# P1_2025-01-25.net
KiCad netlist of a schematic drawn in EasyEDA Pro
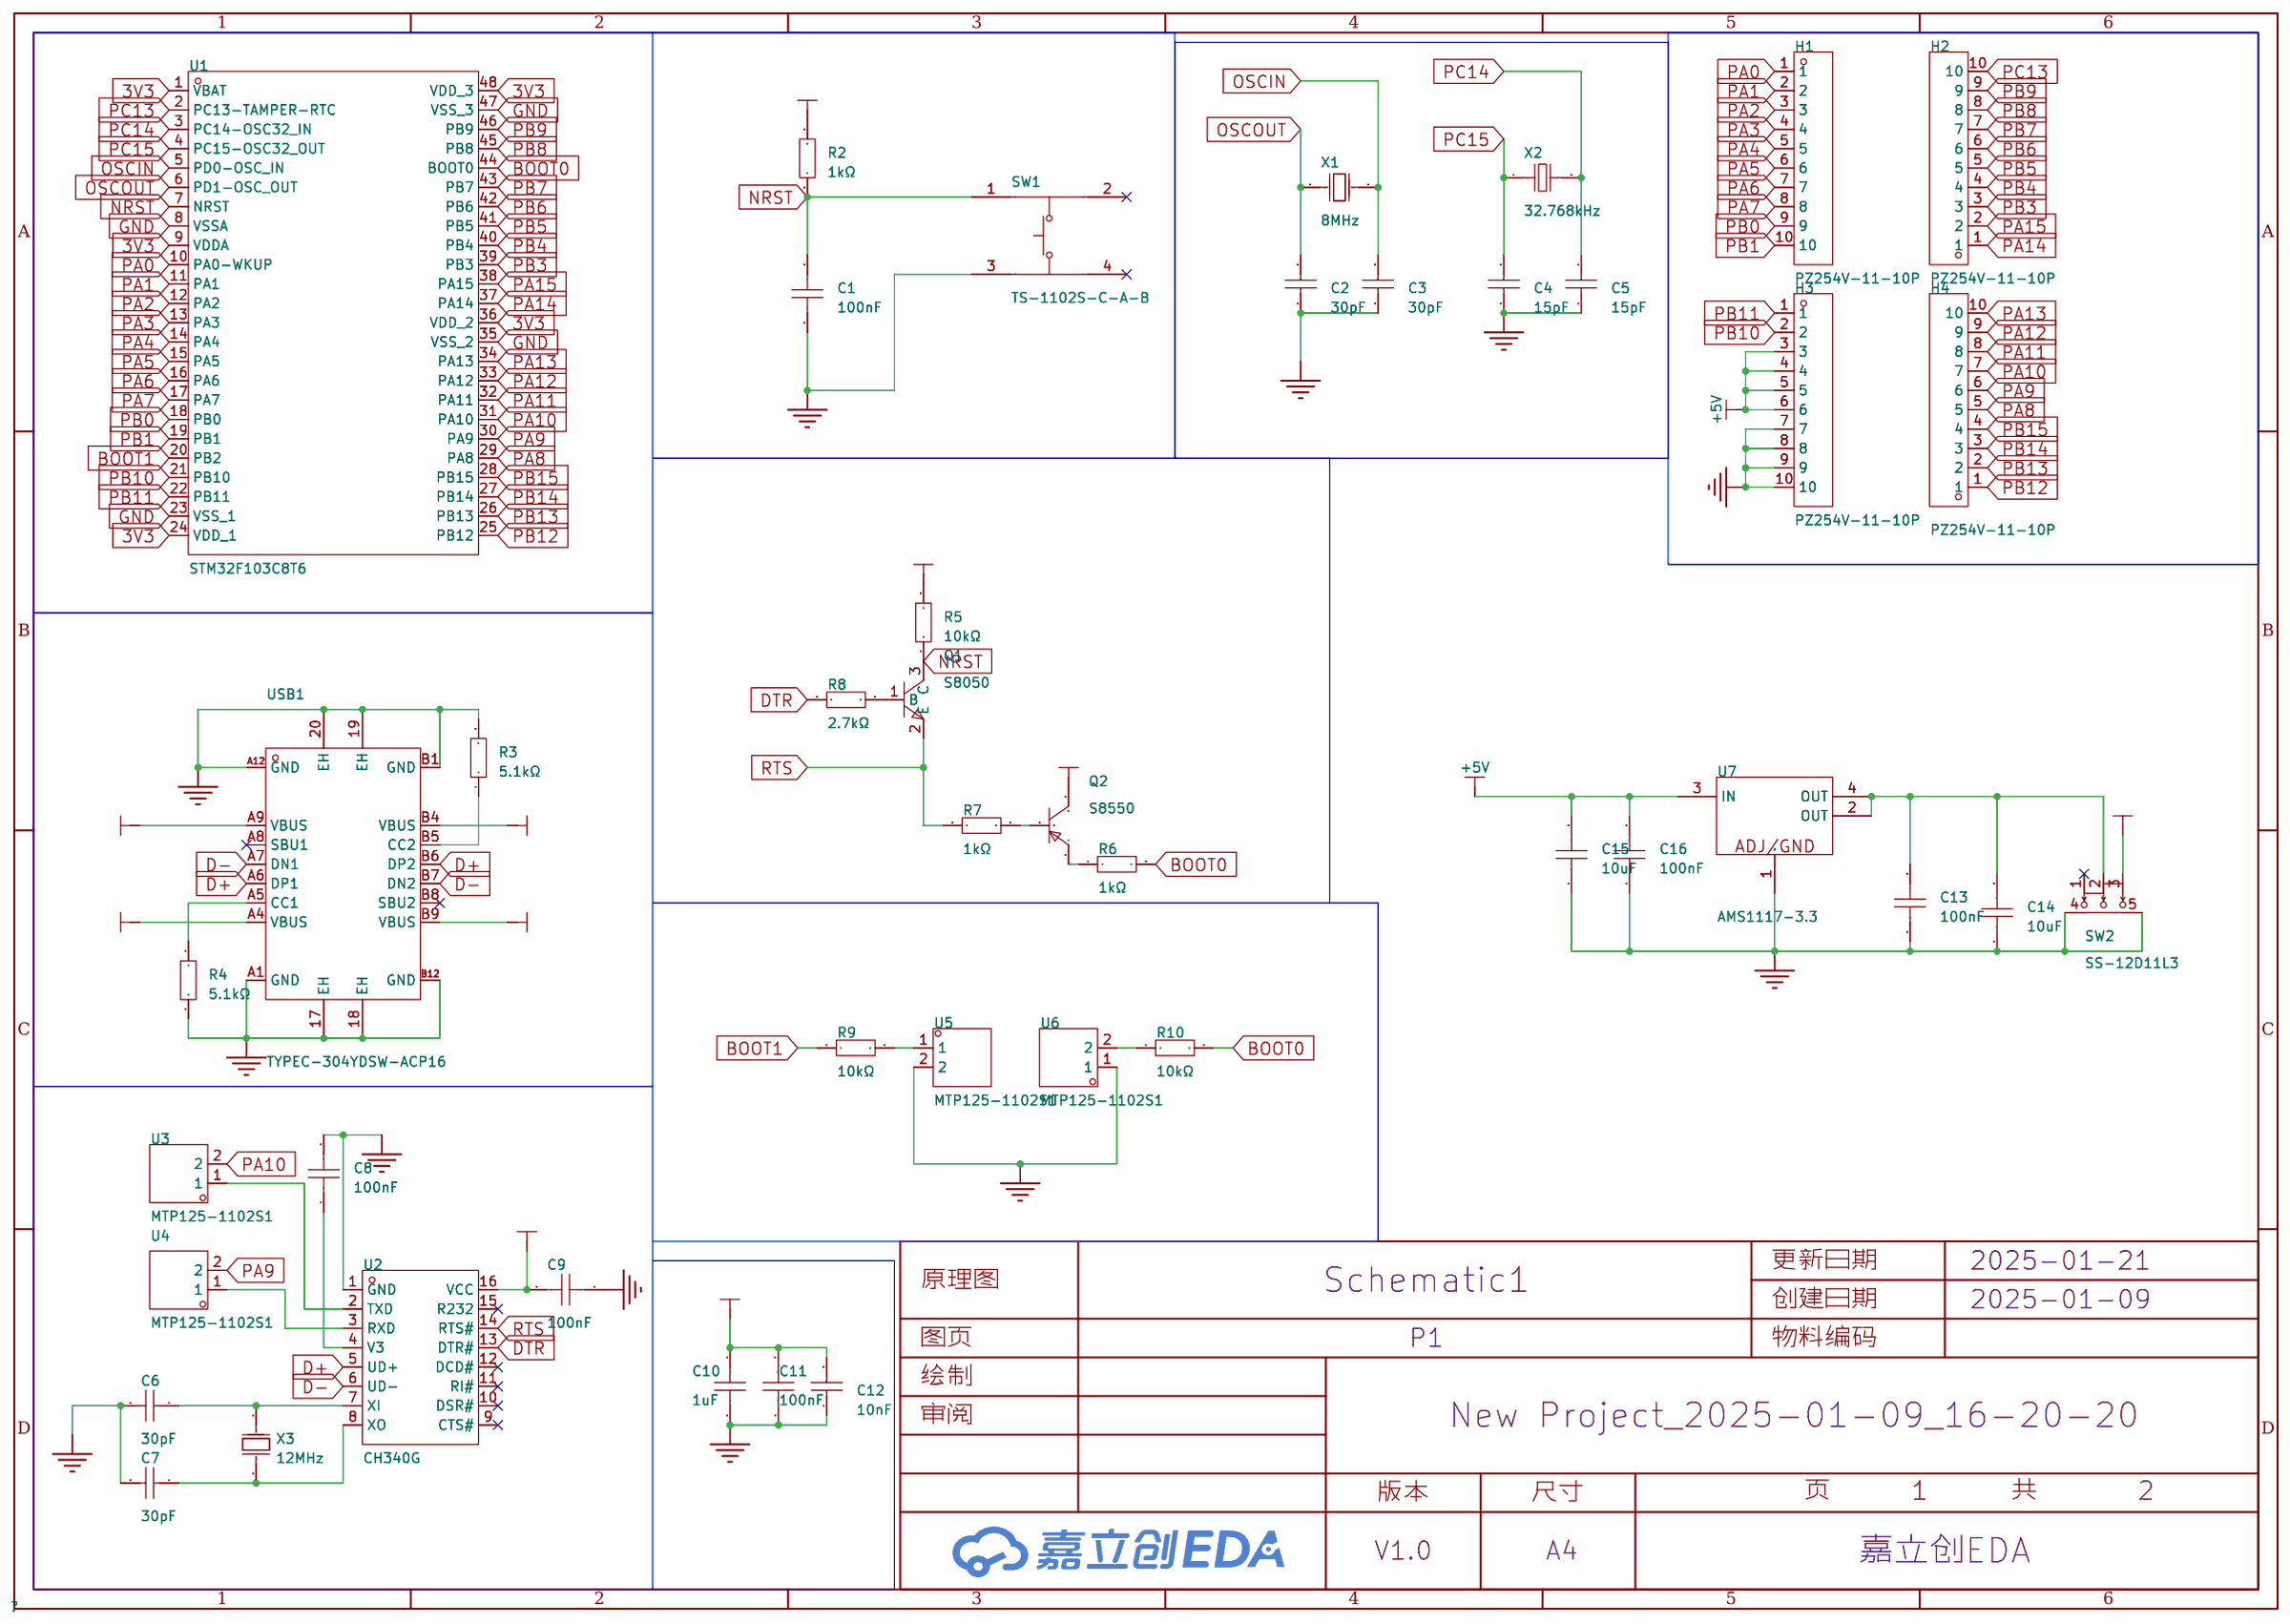
[diagram p0: schematic sheet]

(export (version "E")
  (design (tool "Eeschema 10.0.6"))
  (components
    (comp (ref "C1")
      (value "100nF")
      (footprint "easyedapro:C0603")
      (description "容值:100nF;精度:±10%;额定电压:50V;材质(温度系数):X7R;")
      (fields
        (field (name "Manufacturer Part") "CGA0603X7R104K500JT")
        (field (name "Manufacturer") "HRE(芯声)")
      )
      (libsource (lib "easyedapro") (part "CGA0603X7R104K500JT"))
    )
    (comp (ref "C2")
      (value "30pF")
      (footprint "easyedapro:C0603")
      (description "容值:30pF;精度:±5%;额定电压:50V;材质(温度系数):C0G;")
      (fields (field (name "Manufacturer Part") "0603CG300J500NT") (field (name "Manufacturer") "FH(风华)"))
      (libsource (lib "easyedapro") (part "0603CG300J500NT"))
    )
    (comp (ref "C3")
      (value "30pF")
      (footprint "easyedapro:C0603")
      (description "容值:30pF;精度:±5%;额定电压:50V;材质(温度系数):C0G;")
      (fields (field (name "Manufacturer Part") "0603CG300J500NT") (field (name "Manufacturer") "FH(风华)"))
      (libsource (lib "easyedapro") (part "0603CG300J500NT"))
    )
    (comp (ref "C4")
      (value "15pF")
      (footprint "easyedapro:C0603")
      (description "容值:15pF;精度:±5%;额定电压:50V;材质(温度系数):C0G;")
      (fields
        (field (name "Manufacturer Part") "CL10C150JB8NNNC")
        (field (name "Manufacturer") "SAMSUNG(三星)")
      )
      (libsource (lib "easyedapro") (part "CL10C150JB8NNNC"))
    )
    (comp (ref "C5")
      (value "15pF")
      (footprint "easyedapro:C0603")
      (description "容值:15pF;精度:±5%;额定电压:50V;材质(温度系数):C0G;")
      (fields
        (field (name "Manufacturer Part") "CL10C150JB8NNNC")
        (field (name "Manufacturer") "SAMSUNG(三星)")
      )
      (libsource (lib "easyedapro") (part "CL10C150JB8NNNC"))
    )
    (comp (ref "C6")
      (value "30pF")
      (footprint "easyedapro:C0603")
      (description "容值:30pF;精度:±5%;额定电压:50V;材质(温度系数):C0G;")
      (fields (field (name "Manufacturer Part") "0603CG300J500NT") (field (name "Manufacturer") "FH(风华)"))
      (libsource (lib "easyedapro") (part "0603CG300J500NT"))
    )
    (comp (ref "C7")
      (value "30pF")
      (footprint "easyedapro:C0603")
      (description "容值:30pF;精度:±5%;额定电压:50V;材质(温度系数):C0G;")
      (fields (field (name "Manufacturer Part") "0603CG300J500NT") (field (name "Manufacturer") "FH(风华)"))
      (libsource (lib "easyedapro") (part "0603CG300J500NT"))
    )
    (comp (ref "C8")
      (value "100nF")
      (footprint "easyedapro:C0603")
      (description "容值:100nF;精度:±10%;额定电压:50V;材质(温度系数):X7R;")
      (fields
        (field (name "Manufacturer Part") "CGA0603X7R104K500JT")
        (field (name "Manufacturer") "HRE(芯声)")
      )
      (libsource (lib "easyedapro") (part "CGA0603X7R104K500JT"))
    )
    (comp (ref "C9")
      (value "100nF")
      (footprint "easyedapro:C0603")
      (description "容值:100nF;精度:±10%;额定电压:50V;材质(温度系数):X7R;")
      (fields
        (field (name "Manufacturer Part") "CGA0603X7R104K500JT")
        (field (name "Manufacturer") "HRE(芯声)")
      )
      (libsource (lib "easyedapro") (part "CGA0603X7R104K500JT"))
    )
    (comp (ref "C10")
      (value "1uF")
      (footprint "easyedapro:C0603")
      (description "容值:1uF;精度:±10%;额定电压:50V;材质(温度系数):X5R;")
      (fields
        (field (name "Manufacturer Part") "CL10A105KB8NNNC")
        (field (name "Manufacturer") "SAMSUNG(三星)")
      )
      (libsource (lib "easyedapro") (part "CL10A105KB8NNNC"))
    )
    (comp (ref "C11")
      (value "100nF")
      (footprint "easyedapro:C0603")
      (description "容值:100nF;精度:±10%;额定电压:50V;材质(温度系数):X7R;")
      (fields
        (field (name "Manufacturer Part") "CGA0603X7R104K500JT")
        (field (name "Manufacturer") "HRE(芯声)")
      )
      (libsource (lib "easyedapro") (part "CGA0603X7R104K500JT"))
    )
    (comp (ref "C12")
      (value "10nF")
      (footprint "easyedapro:C0603")
      (description "容值:10nF;精度:±10%;额定电压:50V;材质(温度系数):X7R;")
      (fields
        (field (name "Manufacturer Part") "CC0603KRX7R9BB103")
        (field (name "Manufacturer") "YAGEO(国巨)")
      )
      (libsource (lib "easyedapro") (part "CC0603KRX7R9BB103"))
    )
    (comp (ref "C13")
      (value "100nF")
      (footprint "easyedapro:C0603")
      (description "容值:100nF;精度:±10%;额定电压:50V;材质(温度系数):X7R;")
      (fields
        (field (name "Manufacturer Part") "CGA0603X7R104K500JT")
        (field (name "Manufacturer") "HRE(芯声)")
      )
      (libsource (lib "easyedapro") (part "CGA0603X7R104K500JT"))
    )
    (comp (ref "C14")
      (value "10uF")
      (footprint "easyedapro:C0603")
      (description "容值:10uF;精度:±10%;额定电压:10V;材质(温度系数):X5R;")
      (fields
        (field (name "Manufacturer Part") "CGA0603X5R106K100JT")
        (field (name "Manufacturer") "HRE(芯声)")
      )
      (libsource (lib "easyedapro") (part "CGA0603X5R106K100JT"))
    )
    (comp (ref "C15")
      (value "10uF")
      (footprint "easyedapro:C0603")
      (description "容值:10uF;精度:±10%;额定电压:10V;材质(温度系数):X5R;")
      (fields
        (field (name "Manufacturer Part") "CGA0603X5R106K100JT")
        (field (name "Manufacturer") "HRE(芯声)")
      )
      (libsource (lib "easyedapro") (part "CGA0603X5R106K100JT"))
    )
    (comp (ref "C16")
      (value "100nF")
      (footprint "easyedapro:C0603")
      (description "容值:100nF;精度:±10%;额定电压:50V;材质(温度系数):X7R;")
      (fields
        (field (name "Manufacturer Part") "CGA0603X7R104K500JT")
        (field (name "Manufacturer") "HRE(芯声)")
      )
      (libsource (lib "easyedapro") (part "CGA0603X7R104K500JT"))
    )
    (comp (ref "H1")
      (value "PZ254V-11-10P")
      (footprint "easyedapro:HDR-TH_10P-P2.54-V-M")
      (fields (field (name "Manufacturer") "XFCN(兴飞)"))
      (libsource (lib "easyedapro") (part "PZ254V-11-10P"))
    )
    (comp (ref "H2")
      (value "PZ254V-11-10P")
      (footprint "easyedapro:HDR-TH_10P-P2.54-V-M")
      (fields (field (name "Manufacturer") "XFCN(兴飞)"))
      (libsource (lib "easyedapro") (part "PZ254V-11-10P"))
    )
    (comp (ref "H3")
      (value "PZ254V-11-10P")
      (footprint "easyedapro:HDR-TH_10P-P2.54-V-M")
      (fields (field (name "Manufacturer") "XFCN(兴飞)"))
      (libsource (lib "easyedapro") (part "PZ254V-11-10P"))
    )
    (comp (ref "H4")
      (value "PZ254V-11-10P")
      (footprint "easyedapro:HDR-TH_10P-P2.54-V-M")
      (fields (field (name "Manufacturer") "XFCN(兴飞)"))
      (libsource (lib "easyedapro") (part "PZ254V-11-10P"))
    )
    (comp (ref "Q1")
      (value "S8050")
      (footprint "easyedapro:SOT-23-3_L2.9-W1.3-P1.90-LS2.4-BR")
      (description "晶体管类型:-;集电极电流(Ic):800mA;集射极击穿电压(Vceo):40V;功率(Pd):300mW;直流电流增益(hFE@Ic,Vce):200@50mA,1V;")
      (fields (field (name "Manufacturer") "FOSAN(富信)"))
      (libsource (lib "easyedapro") (part "S8050_C2926165"))
    )
    (comp (ref "Q2")
      (value "S8550")
      (footprint "easyedapro:SOT-23-3_L2.9-W1.3-P1.90-LS2.4-BR")
      (description "晶体管类型:PNP;集电极电流(Ic):500mA;集射极击穿电压(Vceo):25V;功率(Pd):300mW;直流电流增益(hFE@Ic,Vce):120@50mA,1V;")
      (fields (field (name "Manufacturer") "UMW(友台半导体)"))
      (libsource (lib "easyedapro") (part "S8550_C545533"))
    )
    (comp (ref "R2")
      (value "1kΩ")
      (footprint "easyedapro:R0603")
      (description "电阻类型:厚膜电阻;阻值:1kΩ;精度:±1%;功率:100mW;最大工作电压:75V;温度系数:±100ppm/°C;")
      (fields
        (field (name "Manufacturer Part") "0603WAF1001T5E")
        (field (name "Manufacturer") "UNI-ROYAL(厚声)")
      )
      (libsource (lib "easyedapro") (part "0603WAF1001T5E"))
    )
    (comp (ref "R3")
      (value "5.1kΩ")
      (footprint "easyedapro:R0603")
      (description "电阻类型:厚膜电阻;阻值:5.1kΩ;精度:±1%;功率:100mW;最大工作电压:75V;温度系数:±100ppm/°C;")
      (fields
        (field (name "Manufacturer Part") "0603WAF5101T5E")
        (field (name "Manufacturer") "UNI-ROYAL(厚声)")
      )
      (libsource (lib "easyedapro") (part "0603WAF5101T5E"))
    )
    (comp (ref "R4")
      (value "5.1kΩ")
      (footprint "easyedapro:R0603")
      (description "电阻类型:厚膜电阻;阻值:5.1kΩ;精度:±1%;功率:100mW;最大工作电压:75V;温度系数:±100ppm/°C;")
      (fields
        (field (name "Manufacturer Part") "0603WAF5101T5E")
        (field (name "Manufacturer") "UNI-ROYAL(厚声)")
      )
      (libsource (lib "easyedapro") (part "0603WAF5101T5E"))
    )
    (comp (ref "R5")
      (value "10kΩ")
      (footprint "easyedapro:R0603")
      (description "电阻类型:厚膜电阻;阻值:10kΩ;精度:±1%;功率:100mW;最大工作电压:75V;温度系数:±100ppm/°C;")
      (fields
        (field (name "Manufacturer Part") "0603WAF1002T5E")
        (field (name "Manufacturer") "UNI-ROYAL(厚声)")
      )
      (libsource (lib "easyedapro") (part "0603WAF1002T5E"))
    )
    (comp (ref "R6")
      (value "1kΩ")
      (footprint "easyedapro:R0603")
      (description "电阻类型:厚膜电阻;阻值:1kΩ;精度:±1%;功率:100mW;最大工作电压:75V;温度系数:±100ppm/°C;")
      (fields
        (field (name "Manufacturer Part") "0603WAF1001T5E")
        (field (name "Manufacturer") "UNI-ROYAL(厚声)")
      )
      (libsource (lib "easyedapro") (part "0603WAF1001T5E"))
    )
    (comp (ref "R7")
      (value "1kΩ")
      (footprint "easyedapro:R0603")
      (description "电阻类型:厚膜电阻;阻值:1kΩ;精度:±1%;功率:100mW;最大工作电压:75V;温度系数:±100ppm/°C;")
      (fields
        (field (name "Manufacturer Part") "0603WAF1001T5E")
        (field (name "Manufacturer") "UNI-ROYAL(厚声)")
      )
      (libsource (lib "easyedapro") (part "0603WAF1001T5E"))
    )
    (comp (ref "R8")
      (value "2.7kΩ")
      (footprint "easyedapro:R0603")
      (description "电阻类型:厚膜电阻;阻值:2.7kΩ;精度:±1%;功率:100mW;最大工作电压:75V;温度系数:±100ppm/°C;")
      (fields
        (field (name "Manufacturer Part") "0603WAF2701T5E")
        (field (name "Manufacturer") "UNI-ROYAL(厚声)")
      )
      (libsource (lib "easyedapro") (part "0603WAF2701T5E"))
    )
    (comp (ref "R9")
      (value "10kΩ")
      (footprint "easyedapro:R0603")
      (description "电阻类型:厚膜电阻;阻值:10kΩ;精度:±1%;功率:100mW;最大工作电压:75V;温度系数:±100ppm/°C;")
      (fields
        (field (name "Manufacturer Part") "0603WAF1002T5E")
        (field (name "Manufacturer") "UNI-ROYAL(厚声)")
      )
      (libsource (lib "easyedapro") (part "0603WAF1002T5E"))
    )
    (comp (ref "R10")
      (value "10kΩ")
      (footprint "easyedapro:R0603")
      (description "电阻类型:厚膜电阻;阻值:10kΩ;精度:±1%;功率:100mW;最大工作电压:75V;温度系数:±100ppm/°C;")
      (fields
        (field (name "Manufacturer Part") "0603WAF1002T5E")
        (field (name "Manufacturer") "UNI-ROYAL(厚声)")
      )
      (libsource (lib "easyedapro") (part "0603WAF1002T5E"))
    )
    (comp (ref "SW1")
      (value "TS-1102S-C-A-B")
      (footprint "easyedapro:KEY-SMD_4P-L6.0-W6.0-P4.50-LS8.6")
      (fields (field (name "Manufacturer") "XKB Connectivity(中国星坤)"))
      (libsource (lib "easyedapro") (part "TS-1102S-C-A-B"))
    )
    (comp (ref "SW2")
      (value "SS-12D11L3")
      (footprint "easyedapro:SW-TH_SS-12D11L3")
      (description "电路结构:单刀双掷;安装方式:弯插;开关颜色:黑色;额定电流(DC):3A;额定电压(DC):125V;额定电流(AC):3A;额定电压(AC):125V;机械寿命:1万次;")
      (fields (field (name "Manufacturer") "XKB Connectivity(中国星坤)"))
      (libsource (lib "easyedapro") (part "SS-12D11L3"))
    )
    (comp (ref "U1")
      (value "STM32F103C8T6")
      (footprint "easyedapro:LQFP-48_L7.0-W7.0-P0.50-LS9.0-BL")
      (description "CPU内核:ARM-M3;CPU最大主频:72MHz;应用领域:-;")
      (fields (field (name "Manufacturer") "ST(意法半导体)"))
      (libsource (lib "easyedapro") (part "STM32F103C8T6"))
    )
    (comp (ref "U2")
      (value "CH340G")
      (footprint "easyedapro:SOIC-16_L9.9-W3.9-P1.27-LS6.0-BL")
      (description "应用功能:USB转UART;接口协议:USB 2.0;数据速率:2Mbps;")
      (fields (field (name "Manufacturer") "WCH(南京沁恒)"))
      (libsource (lib "easyedapro") (part "CH340G"))
    )
    (comp (ref "U3")
      (value "MTP125-1102S1")
      (footprint "easyedapro:HDR-TH_2P-P2.54-V-M-1")
      (fields (field (name "Manufacturer") "MINTRON(明硕)"))
      (libsource (lib "easyedapro") (part "MTP125-1102S1"))
    )
    (comp (ref "U4")
      (value "MTP125-1102S1")
      (footprint "easyedapro:HDR-TH_2P-P2.54-V-M-1")
      (fields (field (name "Manufacturer") "MINTRON(明硕)"))
      (libsource (lib "easyedapro") (part "MTP125-1102S1"))
    )
    (comp (ref "U5")
      (value "MTP125-1102S1")
      (footprint "easyedapro:HDR-TH_2P-P2.54-V-M-1")
      (fields (field (name "Manufacturer") "MINTRON(明硕)"))
      (libsource (lib "easyedapro") (part "MTP125-1102S1"))
    )
    (comp (ref "U6")
      (value "MTP125-1102S1")
      (footprint "easyedapro:HDR-TH_2P-P2.54-V-M-1")
      (fields (field (name "Manufacturer") "MINTRON(明硕)"))
      (libsource (lib "easyedapro") (part "MTP125-1102S1"))
    )
    (comp (ref "U7")
      (value "AMS1117-3.3")
      (footprint "easyedapro:SOT-223-3_L6.4-W3.5-P2.30-LS7.0-BR")
      (fields (field (name "Manufacturer") "国芯佳品"))
      (libsource (lib "easyedapro") (part "AMS1117-3.3_C2992570"))
    )
    (comp (ref "USB1")
      (value "TYPEC-304YDSW-ACP16")
      (footprint "easyedapro:USB-C-SMD_TYPEC-304YDSW-ACP16")
      (fields (field (name "Manufacturer") "XUNPU(讯普)"))
      (libsource (lib "easyedapro") (part "TYPEC-304YDSW-ACP16"))
    )
    (comp (ref "X1")
      (value "8MHz")
      (footprint "easyedapro:OSC-TH_L10.0-W4.5-P5.00")
      (description "晶振类型:直插晶振;频率:8MHz;常温频差:±20ppm;外接负载电容:20pF;频率稳定度(全温):±30ppm;")
      (fields (field (name "Manufacturer Part") "X49SD8MSD2SC") (field (name "Manufacturer") "YXC(扬兴晶振)"))
      (libsource (lib "easyedapro") (part "X49SD8MSD2SC"))
    )
    (comp (ref "X2")
      (value "32.768kHz")
      (footprint "easyedapro:CRYSTAL-SMD_L7.0-W3.2-LS7.5")
      (description "频率:32.768kHz;常温频差:±20ppm;外接负载电容:12.5pF;频率稳定度(全温):±10ppm;")
      (fields
        (field (name "Manufacturer Part") "HY32768KSMD3068YA2R30")
        (field (name "Manufacturer") "Huiyuan crystal(惠源晶工)")
      )
      (libsource (lib "easyedapro") (part "HY32768KSMD3068YA2R30"))
    )
    (comp (ref "X3")
      (value "12MHz")
      (footprint "easyedapro:HC-49US_L11.5-W4.5-P4.88")
      (description "晶振类型:直插晶振;频率:12MHz;常温频差:±20ppm;外接负载电容:20pF;频率稳定度(全温):±30ppm;")
      (fields (field (name "Manufacturer Part") "X49SD12MSD2SC") (field (name "Manufacturer") "YXC(扬兴晶振)"))
      (libsource (lib "easyedapro") (part "X49SD12MSD2SC"))
    )
  )
  (nets
    (net (code "1") (name "+5V") (class "Default")
      (node (ref "C15") (pin "2") (pinfunction "2_2") (pintype "unspecified"))
      (node (ref "C16") (pin "2") (pinfunction "2_2") (pintype "unspecified"))
      (node (ref "H3") (pin "3") (pinfunction "3_3") (pintype "unspecified"))
      (node (ref "H3") (pin "4") (pinfunction "4_4") (pintype "unspecified"))
      (node (ref "H3") (pin "5") (pinfunction "5_5") (pintype "unspecified"))
      (node (ref "H3") (pin "6") (pinfunction "6_6") (pintype "unspecified"))
      (node (ref "U7") (pin "3") (pinfunction "IN_3") (pintype "unspecified"))
    )
    (net (code "2") (name "+5VUSB") (class "Default")
      (node (ref "C9") (pin "2") (pinfunction "2_2") (pintype "unspecified"))
      (node (ref "U2") (pin "16") (pinfunction "VCC_16") (pintype "unspecified"))
      (node (ref "USB1") (pin "A4") (pinfunction "VBUS_A4") (pintype "unspecified"))
      (node (ref "USB1") (pin "A9") (pinfunction "VBUS_A9") (pintype "unspecified"))
      (node (ref "USB1") (pin "B4") (pinfunction "VBUS_B4") (pintype "unspecified"))
      (node (ref "USB1") (pin "B9") (pinfunction "VBUS_B9") (pintype "unspecified"))
    )
    (net (code "3") (name "3V3") (class "Default")
      (node (ref "C10") (pin "2") (pinfunction "2_2") (pintype "unspecified"))
      (node (ref "C11") (pin "2") (pinfunction "2_2") (pintype "unspecified"))
      (node (ref "C12") (pin "2") (pinfunction "2_2") (pintype "input"))
      (node (ref "Q2") (pin "3") (pinfunction "C_3") (pintype "input"))
      (node (ref "R2") (pin "2") (pinfunction "2_2") (pintype "input"))
      (node (ref "R5") (pin "2") (pinfunction "2_2") (pintype "input"))
      (node (ref "SW2") (pin "3") (pinfunction "3_3") (pintype "unspecified"))
      (node (ref "U1") (pin "1") (pinfunction "VBAT_1") (pintype "unspecified"))
      (node (ref "U1") (pin "24") (pinfunction "VDD_1_24") (pintype "unspecified"))
      (node (ref "U1") (pin "36") (pinfunction "VDD_2_36") (pintype "unspecified"))
      (node (ref "U1") (pin "48") (pinfunction "VDD_3_48") (pintype "unspecified"))
      (node (ref "U1") (pin "9") (pinfunction "VDDA_9") (pintype "unspecified"))
    )
    (net (code "4") (name "BOOT0") (class "Default")
      (node (ref "R10") (pin "2") (pinfunction "2_2") (pintype "input"))
      (node (ref "R6") (pin "2") (pinfunction "2_2") (pintype "input"))
      (node (ref "U1") (pin "44") (pinfunction "BOOT0_44") (pintype "unspecified"))
    )
    (net (code "5") (name "BOOT1") (class "Default")
      (node (ref "R9") (pin "1") (pinfunction "1_1") (pintype "input"))
      (node (ref "U1") (pin "20") (pinfunction "PB2_20") (pintype "unspecified"))
    )
    (net (code "6") (name "D+") (class "Default")
      (node (ref "U2") (pin "5") (pinfunction "UD+_5") (pintype "unspecified"))
      (node (ref "USB1") (pin "A6") (pinfunction "DP1_A6") (pintype "unspecified"))
      (node (ref "USB1") (pin "B6") (pinfunction "DP2_B6") (pintype "unspecified"))
    )
    (net (code "7") (name "D-") (class "Default")
      (node (ref "U2") (pin "6") (pinfunction "UD-_6") (pintype "unspecified"))
      (node (ref "USB1") (pin "A7") (pinfunction "DN1_A7") (pintype "unspecified"))
      (node (ref "USB1") (pin "B7") (pinfunction "DN2_B7") (pintype "unspecified"))
    )
    (net (code "8") (name "DTR") (class "Default")
      (node (ref "R8") (pin "1") (pinfunction "1_1") (pintype "input"))
      (node (ref "U2") (pin "13") (pinfunction "DTR#_13") (pintype "unspecified"))
    )
    (net (code "9") (name "GND") (class "Default")
      (node (ref "C1") (pin "1") (pinfunction "1_1") (pintype "unspecified"))
      (node (ref "C10") (pin "1") (pinfunction "1_1") (pintype "unspecified"))
      (node (ref "C11") (pin "1") (pinfunction "1_1") (pintype "unspecified"))
      (node (ref "C12") (pin "1") (pinfunction "1_1") (pintype "input"))
      (node (ref "C13") (pin "1") (pinfunction "1_1") (pintype "unspecified"))
      (node (ref "C14") (pin "1") (pinfunction "1_1") (pintype "unspecified"))
      (node (ref "C15") (pin "1") (pinfunction "1_1") (pintype "unspecified"))
      (node (ref "C16") (pin "1") (pinfunction "1_1") (pintype "unspecified"))
      (node (ref "C2") (pin "1") (pinfunction "1_1") (pintype "input"))
      (node (ref "C3") (pin "1") (pinfunction "1_1") (pintype "input"))
      (node (ref "C4") (pin "1") (pinfunction "1_1") (pintype "input"))
      (node (ref "C5") (pin "1") (pinfunction "1_1") (pintype "input"))
      (node (ref "C6") (pin "2") (pinfunction "2_2") (pintype "input"))
      (node (ref "C7") (pin "2") (pinfunction "2_2") (pintype "input"))
      (node (ref "C8") (pin "2") (pinfunction "2_2") (pintype "unspecified"))
      (node (ref "C9") (pin "1") (pinfunction "1_1") (pintype "unspecified"))
      (node (ref "H3") (pin "10") (pinfunction "10_10") (pintype "unspecified"))
      (node (ref "H3") (pin "7") (pinfunction "7_7") (pintype "unspecified"))
      (node (ref "H3") (pin "8") (pinfunction "8_8") (pintype "unspecified"))
      (node (ref "H3") (pin "9") (pinfunction "9_9") (pintype "unspecified"))
      (node (ref "R3") (pin "2") (pinfunction "2_2") (pintype "input"))
      (node (ref "R4") (pin "1") (pinfunction "1_1") (pintype "input"))
      (node (ref "SW1") (pin "3") (pinfunction "3_3") (pintype "unspecified"))
      (node (ref "SW2") (pin "4") (pinfunction "4_4") (pintype "unspecified"))
      (node (ref "SW2") (pin "5") (pinfunction "5_5") (pintype "unspecified"))
      (node (ref "U1") (pin "23") (pinfunction "VSS_1_23") (pintype "unspecified"))
      (node (ref "U1") (pin "35") (pinfunction "VSS_2_35") (pintype "unspecified"))
      (node (ref "U1") (pin "47") (pinfunction "VSS_3_47") (pintype "unspecified"))
      (node (ref "U1") (pin "8") (pinfunction "VSSA_8") (pintype "unspecified"))
      (node (ref "U2") (pin "1") (pinfunction "GND_1") (pintype "unspecified"))
      (node (ref "U5") (pin "2") (pinfunction "2_2") (pintype "unspecified"))
      (node (ref "U6") (pin "1") (pinfunction "1_1") (pintype "unspecified"))
      (node (ref "U7") (pin "1") (pinfunction "ADJ/GND_1") (pintype "unspecified"))
      (node (ref "USB1") (pin "17") (pinfunction "EH_17") (pintype "unspecified"))
      (node (ref "USB1") (pin "18") (pinfunction "EH_18") (pintype "unspecified"))
      (node (ref "USB1") (pin "19") (pinfunction "EH_19") (pintype "unspecified"))
      (node (ref "USB1") (pin "20") (pinfunction "EH_20") (pintype "unspecified"))
      (node (ref "USB1") (pin "A1") (pinfunction "GND_A1") (pintype "unspecified"))
      (node (ref "USB1") (pin "A12") (pinfunction "GND_A12") (pintype "unspecified"))
      (node (ref "USB1") (pin "B1") (pinfunction "GND_B1") (pintype "unspecified"))
      (node (ref "USB1") (pin "B12") (pinfunction "GND_B12") (pintype "unspecified"))
    )
    (net (code "10") (name "NRST") (class "Default")
      (node (ref "C1") (pin "2") (pinfunction "2_2") (pintype "unspecified"))
      (node (ref "Q1") (pin "3") (pinfunction "C_3") (pintype "input"))
      (node (ref "R2") (pin "1") (pinfunction "1_1") (pintype "input"))
      (node (ref "R5") (pin "1") (pinfunction "1_1") (pintype "input"))
      (node (ref "SW1") (pin "1") (pinfunction "1_1") (pintype "unspecified"))
      (node (ref "U1") (pin "7") (pinfunction "NRST_7") (pintype "unspecified"))
    )
    (net (code "11") (name "Net-(C13-Pad2)") (class "Default")
      (node (ref "C13") (pin "2") (pinfunction "2_2") (pintype "unspecified"))
      (node (ref "C14") (pin "2") (pinfunction "2_2") (pintype "unspecified"))
      (node (ref "SW2") (pin "2") (pinfunction "2_2") (pintype "unspecified"))
      (node (ref "U7") (pin "2") (pinfunction "OUT_2") (pintype "unspecified"))
      (node (ref "U7") (pin "4") (pinfunction "OUT_4") (pintype "unspecified"))
    )
    (net (code "12") (name "Net-(Q1-B)") (class "Default")
      (node (ref "Q1") (pin "1") (pinfunction "B_1") (pintype "input"))
      (node (ref "R8") (pin "2") (pinfunction "2_2") (pintype "input"))
    )
    (net (code "13") (name "Net-(Q2-B)") (class "Default")
      (node (ref "Q2") (pin "1") (pinfunction "B_1") (pintype "input"))
      (node (ref "R7") (pin "2") (pinfunction "2_2") (pintype "input"))
    )
    (net (code "14") (name "Net-(Q2-E)") (class "Default")
      (node (ref "Q2") (pin "2") (pinfunction "E_2") (pintype "input"))
      (node (ref "R6") (pin "1") (pinfunction "1_1") (pintype "input"))
    )
    (net (code "15") (name "Net-(R9-Pad2)") (class "Default")
      (node (ref "R9") (pin "2") (pinfunction "2_2") (pintype "input"))
      (node (ref "U5") (pin "1") (pinfunction "1_1") (pintype "unspecified"))
    )
    (net (code "16") (name "Net-(R10-Pad1)") (class "Default")
      (node (ref "R10") (pin "1") (pinfunction "1_1") (pintype "input"))
      (node (ref "U6") (pin "2") (pinfunction "2_2") (pintype "unspecified"))
    )
    (net (code "17") (name "Net-(U2-RXD)") (class "Default")
      (node (ref "U2") (pin "3") (pinfunction "RXD_3") (pintype "unspecified"))
      (node (ref "U4") (pin "1") (pinfunction "1_1") (pintype "unspecified"))
    )
    (net (code "18") (name "Net-(U2-TXD)") (class "Default")
      (node (ref "U2") (pin "2") (pinfunction "TXD_2") (pintype "unspecified"))
      (node (ref "U3") (pin "1") (pinfunction "1_1") (pintype "unspecified"))
    )
    (net (code "19") (name "Net-(U2-V3)") (class "Default")
      (node (ref "C8") (pin "1") (pinfunction "1_1") (pintype "unspecified"))
      (node (ref "U2") (pin "4") (pinfunction "V3_4") (pintype "unspecified"))
    )
    (net (code "20") (name "Net-(U2-XI)") (class "Default")
      (node (ref "C6") (pin "1") (pinfunction "1_1") (pintype "input"))
      (node (ref "U2") (pin "7") (pinfunction "XI_7") (pintype "unspecified"))
      (node (ref "X3") (pin "1") (pinfunction "OSC1_1") (pintype "input"))
    )
    (net (code "21") (name "Net-(U2-XO)") (class "Default")
      (node (ref "C7") (pin "1") (pinfunction "1_1") (pintype "input"))
      (node (ref "U2") (pin "8") (pinfunction "XO_8") (pintype "unspecified"))
      (node (ref "X3") (pin "2") (pinfunction "OSC2_2") (pintype "input"))
    )
    (net (code "22") (name "Net-(USB1-CC1)") (class "Default")
      (node (ref "R4") (pin "2") (pinfunction "2_2") (pintype "input"))
      (node (ref "USB1") (pin "A5") (pinfunction "CC1_A5") (pintype "unspecified"))
    )
    (net (code "23") (name "Net-(USB1-CC2)") (class "Default")
      (node (ref "R3") (pin "1") (pinfunction "1_1") (pintype "input"))
      (node (ref "USB1") (pin "B5") (pinfunction "CC2_B5") (pintype "unspecified"))
    )
    (net (code "24") (name "OSCIN") (class "Default")
      (node (ref "C3") (pin "2") (pinfunction "2_2") (pintype "input"))
      (node (ref "U1") (pin "5") (pinfunction "PD0-OSC_IN_5") (pintype "unspecified"))
      (node (ref "X1") (pin "1") (pinfunction "OSC1_1") (pintype "input"))
    )
    (net (code "25") (name "OSCOUT") (class "Default")
      (node (ref "C2") (pin "2") (pinfunction "2_2") (pintype "input"))
      (node (ref "U1") (pin "6") (pinfunction "PD1-OSC_OUT_6") (pintype "unspecified"))
      (node (ref "X1") (pin "2") (pinfunction "OSC2_2") (pintype "input"))
    )
    (net (code "26") (name "PA0") (class "Default")
      (node (ref "H1") (pin "1") (pinfunction "1_1") (pintype "unspecified"))
      (node (ref "U1") (pin "10") (pinfunction "PA0-WKUP_10") (pintype "unspecified"))
    )
    (net (code "27") (name "PA1") (class "Default")
      (node (ref "H1") (pin "2") (pinfunction "2_2") (pintype "unspecified"))
      (node (ref "U1") (pin "11") (pinfunction "PA1_11") (pintype "unspecified"))
    )
    (net (code "28") (name "PA2") (class "Default")
      (node (ref "H1") (pin "3") (pinfunction "3_3") (pintype "unspecified"))
      (node (ref "U1") (pin "12") (pinfunction "PA2_12") (pintype "unspecified"))
    )
    (net (code "29") (name "PA3") (class "Default")
      (node (ref "H1") (pin "4") (pinfunction "4_4") (pintype "unspecified"))
      (node (ref "U1") (pin "13") (pinfunction "PA3_13") (pintype "unspecified"))
    )
    (net (code "30") (name "PA4") (class "Default")
      (node (ref "H1") (pin "5") (pinfunction "5_5") (pintype "unspecified"))
      (node (ref "U1") (pin "14") (pinfunction "PA4_14") (pintype "unspecified"))
    )
    (net (code "31") (name "PA5") (class "Default")
      (node (ref "H1") (pin "6") (pinfunction "6_6") (pintype "unspecified"))
      (node (ref "U1") (pin "15") (pinfunction "PA5_15") (pintype "unspecified"))
    )
    (net (code "32") (name "PA6") (class "Default")
      (node (ref "H1") (pin "7") (pinfunction "7_7") (pintype "unspecified"))
      (node (ref "U1") (pin "16") (pinfunction "PA6_16") (pintype "unspecified"))
    )
    (net (code "33") (name "PA7") (class "Default")
      (node (ref "H1") (pin "8") (pinfunction "8_8") (pintype "unspecified"))
      (node (ref "U1") (pin "17") (pinfunction "PA7_17") (pintype "unspecified"))
    )
    (net (code "34") (name "PA8") (class "Default")
      (node (ref "H4") (pin "5") (pinfunction "5_5") (pintype "unspecified"))
      (node (ref "U1") (pin "29") (pinfunction "PA8_29") (pintype "unspecified"))
    )
    (net (code "35") (name "PA9") (class "Default")
      (node (ref "H4") (pin "6") (pinfunction "6_6") (pintype "unspecified"))
      (node (ref "U1") (pin "30") (pinfunction "PA9_30") (pintype "unspecified"))
      (node (ref "U4") (pin "2") (pinfunction "2_2") (pintype "unspecified"))
    )
    (net (code "36") (name "PA10") (class "Default")
      (node (ref "H4") (pin "7") (pinfunction "7_7") (pintype "unspecified"))
      (node (ref "U1") (pin "31") (pinfunction "PA10_31") (pintype "unspecified"))
      (node (ref "U3") (pin "2") (pinfunction "2_2") (pintype "unspecified"))
    )
    (net (code "37") (name "PA11") (class "Default")
      (node (ref "H4") (pin "8") (pinfunction "8_8") (pintype "unspecified"))
      (node (ref "U1") (pin "32") (pinfunction "PA11_32") (pintype "unspecified"))
    )
    (net (code "38") (name "PA12") (class "Default")
      (node (ref "H4") (pin "9") (pinfunction "9_9") (pintype "unspecified"))
      (node (ref "U1") (pin "33") (pinfunction "PA12_33") (pintype "unspecified"))
    )
    (net (code "39") (name "PA13") (class "Default")
      (node (ref "H4") (pin "10") (pinfunction "10_10") (pintype "unspecified"))
      (node (ref "U1") (pin "34") (pinfunction "PA13_34") (pintype "unspecified"))
    )
    (net (code "40") (name "PA14") (class "Default")
      (node (ref "H2") (pin "1") (pinfunction "1_1") (pintype "unspecified"))
      (node (ref "U1") (pin "37") (pinfunction "PA14_37") (pintype "unspecified"))
    )
    (net (code "41") (name "PA15") (class "Default")
      (node (ref "H2") (pin "2") (pinfunction "2_2") (pintype "unspecified"))
      (node (ref "U1") (pin "38") (pinfunction "PA15_38") (pintype "unspecified"))
    )
    (net (code "42") (name "PB0") (class "Default")
      (node (ref "H1") (pin "9") (pinfunction "9_9") (pintype "unspecified"))
      (node (ref "U1") (pin "18") (pinfunction "PB0_18") (pintype "unspecified"))
    )
    (net (code "43") (name "PB1") (class "Default")
      (node (ref "H1") (pin "10") (pinfunction "10_10") (pintype "unspecified"))
      (node (ref "U1") (pin "19") (pinfunction "PB1_19") (pintype "unspecified"))
    )
    (net (code "44") (name "PB3") (class "Default")
      (node (ref "H2") (pin "3") (pinfunction "3_3") (pintype "unspecified"))
      (node (ref "U1") (pin "39") (pinfunction "PB3_39") (pintype "unspecified"))
    )
    (net (code "45") (name "PB4") (class "Default")
      (node (ref "H2") (pin "4") (pinfunction "4_4") (pintype "unspecified"))
      (node (ref "U1") (pin "40") (pinfunction "PB4_40") (pintype "unspecified"))
    )
    (net (code "46") (name "PB5") (class "Default")
      (node (ref "H2") (pin "5") (pinfunction "5_5") (pintype "unspecified"))
      (node (ref "U1") (pin "41") (pinfunction "PB5_41") (pintype "unspecified"))
    )
    (net (code "47") (name "PB6") (class "Default")
      (node (ref "H2") (pin "6") (pinfunction "6_6") (pintype "unspecified"))
      (node (ref "U1") (pin "42") (pinfunction "PB6_42") (pintype "unspecified"))
    )
    (net (code "48") (name "PB7") (class "Default")
      (node (ref "H2") (pin "7") (pinfunction "7_7") (pintype "unspecified"))
      (node (ref "U1") (pin "43") (pinfunction "PB7_43") (pintype "unspecified"))
    )
    (net (code "49") (name "PB8") (class "Default")
      (node (ref "H2") (pin "8") (pinfunction "8_8") (pintype "unspecified"))
      (node (ref "U1") (pin "45") (pinfunction "PB8_45") (pintype "unspecified"))
    )
    (net (code "50") (name "PB9") (class "Default")
      (node (ref "H2") (pin "9") (pinfunction "9_9") (pintype "unspecified"))
      (node (ref "U1") (pin "46") (pinfunction "PB9_46") (pintype "unspecified"))
    )
    (net (code "51") (name "PB10") (class "Default")
      (node (ref "H3") (pin "2") (pinfunction "2_2") (pintype "unspecified"))
      (node (ref "U1") (pin "21") (pinfunction "PB10_21") (pintype "unspecified"))
    )
    (net (code "52") (name "PB11") (class "Default")
      (node (ref "H3") (pin "1") (pinfunction "1_1") (pintype "unspecified"))
      (node (ref "U1") (pin "22") (pinfunction "PB11_22") (pintype "unspecified"))
    )
    (net (code "53") (name "PB12") (class "Default")
      (node (ref "H4") (pin "1") (pinfunction "1_1") (pintype "unspecified"))
      (node (ref "U1") (pin "25") (pinfunction "PB12_25") (pintype "unspecified"))
    )
    (net (code "54") (name "PB13") (class "Default")
      (node (ref "H4") (pin "2") (pinfunction "2_2") (pintype "unspecified"))
      (node (ref "U1") (pin "26") (pinfunction "PB13_26") (pintype "unspecified"))
    )
    (net (code "55") (name "PB14") (class "Default")
      (node (ref "H4") (pin "3") (pinfunction "3_3") (pintype "unspecified"))
      (node (ref "U1") (pin "27") (pinfunction "PB14_27") (pintype "unspecified"))
    )
    (net (code "56") (name "PB15") (class "Default")
      (node (ref "H4") (pin "4") (pinfunction "4_4") (pintype "unspecified"))
      (node (ref "U1") (pin "28") (pinfunction "PB15_28") (pintype "unspecified"))
    )
    (net (code "57") (name "PC13") (class "Default")
      (node (ref "H2") (pin "10") (pinfunction "10_10") (pintype "unspecified"))
      (node (ref "U1") (pin "2") (pinfunction "PC13-TAMPER-RTC_2") (pintype "unspecified"))
    )
    (net (code "58") (name "PC14") (class "Default")
      (node (ref "C5") (pin "2") (pinfunction "2_2") (pintype "input"))
      (node (ref "U1") (pin "3") (pinfunction "PC14-OSC32_IN_3") (pintype "unspecified"))
      (node (ref "X2") (pin "2") (pinfunction "2_2") (pintype "unspecified"))
    )
    (net (code "59") (name "PC15") (class "Default")
      (node (ref "C4") (pin "2") (pinfunction "2_2") (pintype "input"))
      (node (ref "U1") (pin "4") (pinfunction "PC15-OSC32_OUT_4") (pintype "unspecified"))
      (node (ref "X2") (pin "1") (pinfunction "1_1") (pintype "unspecified"))
    )
    (net (code "60") (name "RTS") (class "Default")
      (node (ref "Q1") (pin "2") (pinfunction "E_2") (pintype "input"))
      (node (ref "R7") (pin "1") (pinfunction "1_1") (pintype "input"))
      (node (ref "U2") (pin "14") (pinfunction "RTS#_14") (pintype "unspecified"))
    )
    (net (code "61") (name "unconnected-(SW1-Pad2)") (class "Default")
      (node (ref "SW1") (pin "2") (pinfunction "2_2") (pintype "unspecified+no_connect"))
    )
    (net (code "62") (name "unconnected-(SW1-Pad4)") (class "Default")
      (node (ref "SW1") (pin "4") (pinfunction "4_4") (pintype "unspecified+no_connect"))
    )
    (net (code "63") (name "unconnected-(SW2-Pad1)") (class "Default")
      (node (ref "SW2") (pin "1") (pinfunction "1_1") (pintype "unspecified+no_connect"))
    )
    (net (code "64") (name "unconnected-(U2-CTS#-Pad9)") (class "Default")
      (node (ref "U2") (pin "9") (pinfunction "CTS#_9") (pintype "unspecified+no_connect"))
    )
    (net (code "65") (name "unconnected-(U2-DCD#-Pad12)") (class "Default")
      (node (ref "U2") (pin "12") (pinfunction "DCD#_12") (pintype "unspecified+no_connect"))
    )
    (net (code "66") (name "unconnected-(U2-DSR#-Pad10)") (class "Default")
      (node (ref "U2") (pin "10") (pinfunction "DSR#_10") (pintype "unspecified+no_connect"))
    )
    (net (code "67") (name "unconnected-(U2-R232-Pad15)") (class "Default")
      (node (ref "U2") (pin "15") (pinfunction "R232_15") (pintype "unspecified+no_connect"))
    )
    (net (code "68") (name "unconnected-(U2-RI#-Pad11)") (class "Default")
      (node (ref "U2") (pin "11") (pinfunction "RI#_11") (pintype "unspecified+no_connect"))
    )
    (net (code "69") (name "unconnected-(USB1-SBU1-PadA8)") (class "Default")
      (node (ref "USB1") (pin "A8") (pinfunction "SBU1_A8") (pintype "unspecified+no_connect"))
    )
    (net (code "70") (name "unconnected-(USB1-SBU2-PadB8)") (class "Default")
      (node (ref "USB1") (pin "B8") (pinfunction "SBU2_B8") (pintype "unspecified+no_connect"))
    )
  )
)
